# spu-schematic.net
KiCad netlist of a schematic drawn in EAGLE
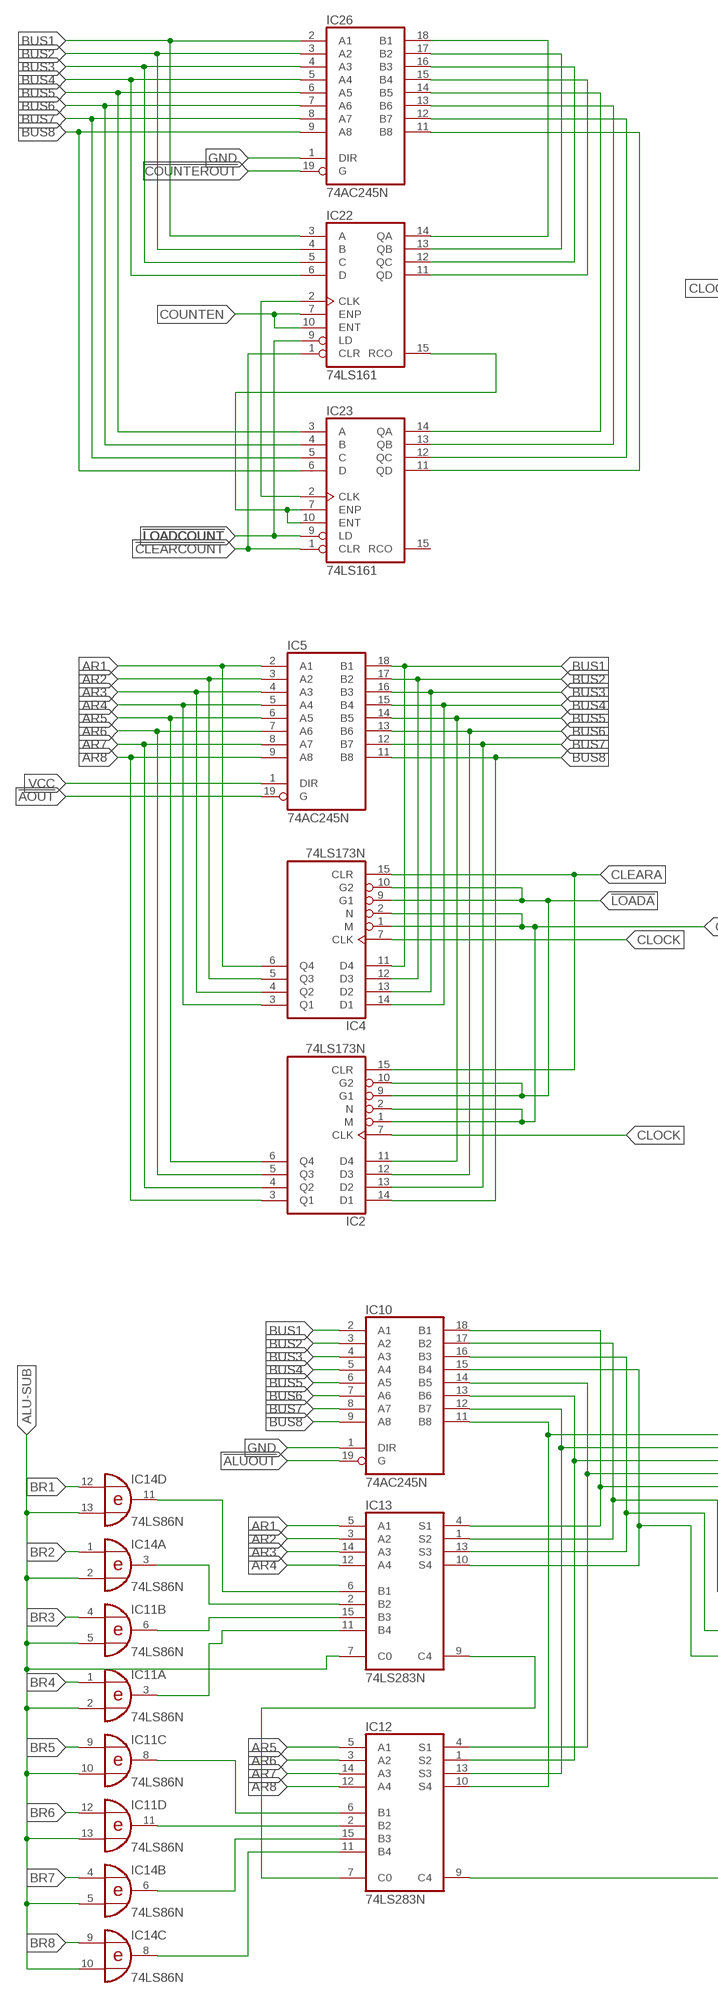
[diagram p0: schematic, sheet 1, part 1 of 2]
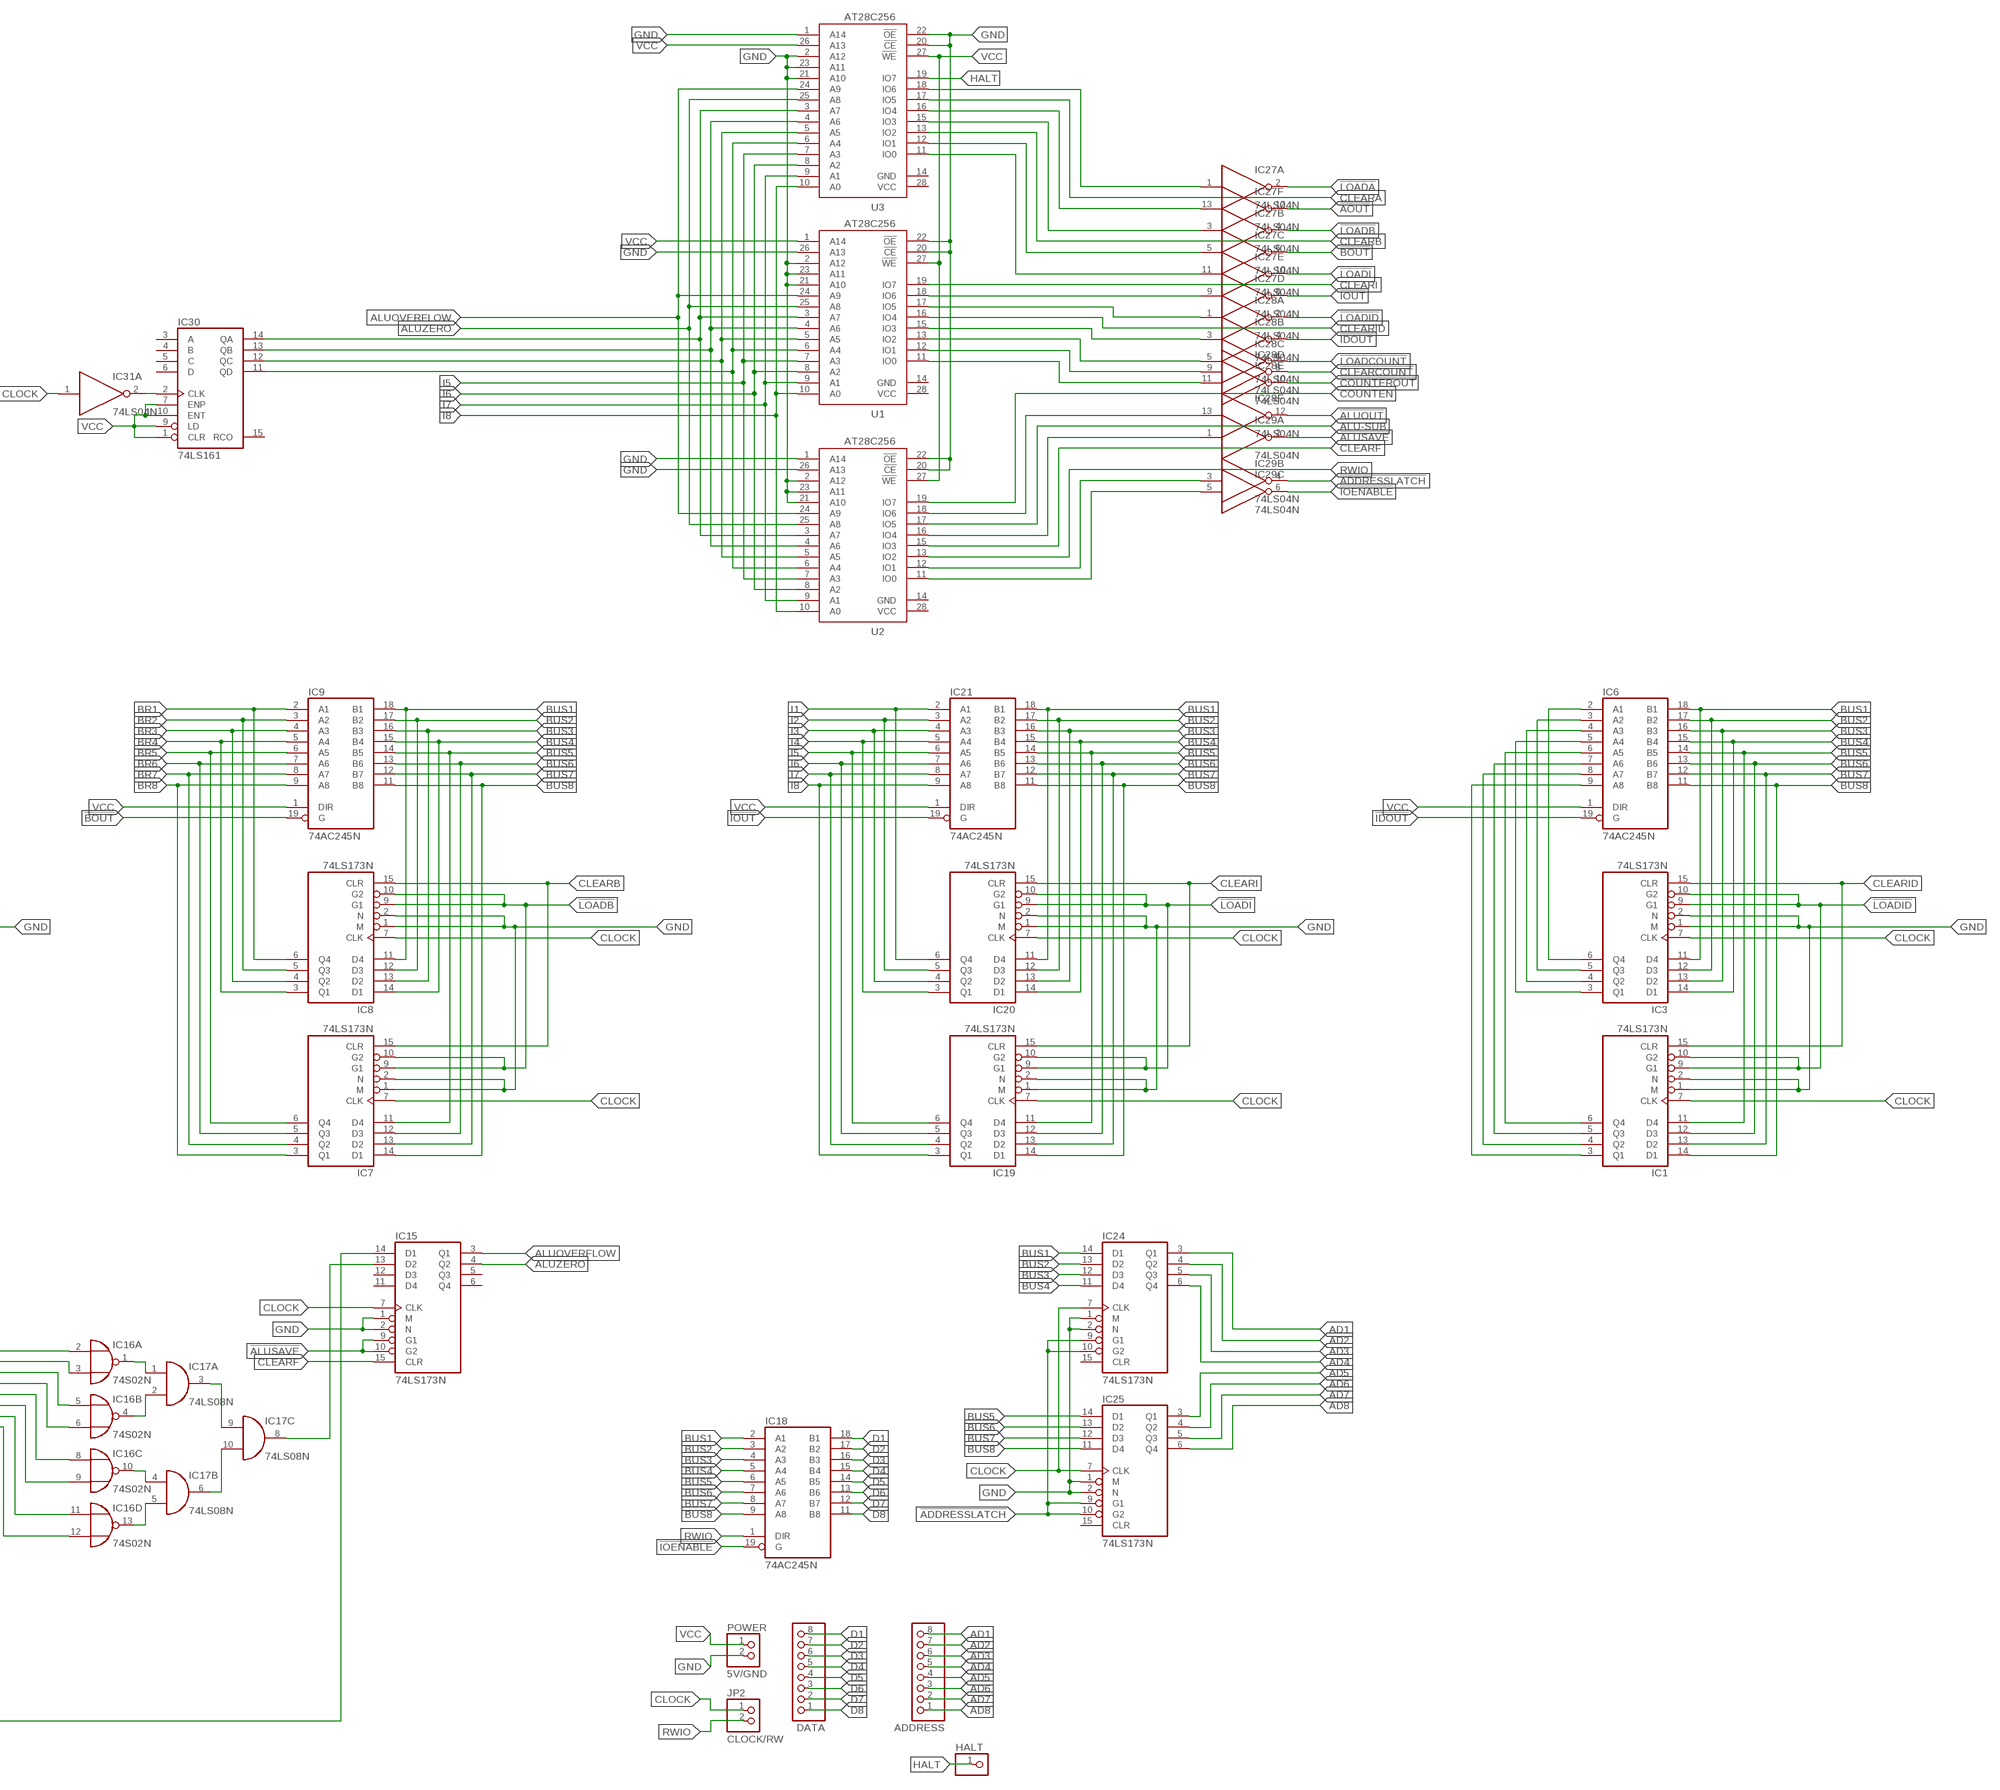
[diagram p1: schematic, sheet 1, part 2 of 2]

(export (version "E")
  (design (tool "Eeschema 10.0.6"))
  (components
    (comp (ref "ADDRESS")
      (value "PINHD-1X8")
      (footprint "eagle-import:1X08")
      (libsource (lib "eagle-import") (part "PINHD-1X8"))
    )
    (comp (ref "DATA")
      (value "PINHD-1X8")
      (footprint "eagle-import:1X08")
      (libsource (lib "eagle-import") (part "PINHD-1X8"))
    )
    (comp (ref "HALT")
      (value "PINHD-1X1")
      (footprint "eagle-import:1X01")
      (libsource (lib "eagle-import") (part "PINHD-1X1"))
    )
    (comp (ref "IC1")
      (value "74LS173N")
      (footprint "eagle-import:DIL16")
      (libsource (lib "eagle-import") (part "74173NLS"))
    )
    (comp (ref "IC2")
      (value "74LS173N")
      (footprint "eagle-import:DIL16")
      (libsource (lib "eagle-import") (part "74173NLS"))
    )
    (comp (ref "IC3")
      (value "74LS173N")
      (footprint "eagle-import:DIL16")
      (libsource (lib "eagle-import") (part "74173NLS"))
    )
    (comp (ref "IC4")
      (value "74LS173N")
      (footprint "eagle-import:DIL16")
      (libsource (lib "eagle-import") (part "74173NLS"))
    )
    (comp (ref "IC5")
      (value "74AC245N")
      (footprint "eagle-import:DIL20")
      (libsource (lib "eagle-import") (part "74245NAC"))
    )
    (comp (ref "IC6")
      (value "74AC245N")
      (footprint "eagle-import:DIL20")
      (libsource (lib "eagle-import") (part "74245NAC"))
    )
    (comp (ref "IC7")
      (value "74LS173N")
      (footprint "eagle-import:DIL16")
      (libsource (lib "eagle-import") (part "74173NLS"))
    )
    (comp (ref "IC8")
      (value "74LS173N")
      (footprint "eagle-import:DIL16")
      (libsource (lib "eagle-import") (part "74173NLS"))
    )
    (comp (ref "IC9")
      (value "74AC245N")
      (footprint "eagle-import:DIL20")
      (libsource (lib "eagle-import") (part "74245NAC"))
    )
    (comp (ref "IC10")
      (value "74AC245N")
      (footprint "eagle-import:DIL20")
      (libsource (lib "eagle-import") (part "74245NAC"))
    )
    (comp (ref "IC11")
      (value "74LS86N")
      (footprint "eagle-import:DIL14")
      (libsource (lib "eagle-import") (part "7486NLS"))
    )
    (comp (ref "IC12")
      (value "74LS283N")
      (footprint "eagle-import:DIL16")
      (libsource (lib "eagle-import") (part "74283NLS"))
    )
    (comp (ref "IC13")
      (value "74LS283N")
      (footprint "eagle-import:DIL16")
      (libsource (lib "eagle-import") (part "74283NLS"))
    )
    (comp (ref "IC14")
      (value "74LS86N")
      (footprint "eagle-import:DIL14")
      (libsource (lib "eagle-import") (part "7486NLS"))
    )
    (comp (ref "IC15")
      (value "74LS173N")
      (footprint "eagle-import:DIL16")
      (libsource (lib "eagle-import") (part "74173NLS"))
    )
    (comp (ref "IC16")
      (value "74S02N")
      (footprint "eagle-import:DIL14")
      (libsource (lib "eagle-import") (part "7402NS"))
    )
    (comp (ref "IC17")
      (value "74LS08N")
      (footprint "eagle-import:DIL14")
      (libsource (lib "eagle-import") (part "7408NLS"))
    )
    (comp (ref "IC18")
      (value "74AC245N")
      (footprint "eagle-import:DIL20")
      (libsource (lib "eagle-import") (part "74245NAC"))
    )
    (comp (ref "IC19")
      (value "74LS173N")
      (footprint "eagle-import:DIL16")
      (libsource (lib "eagle-import") (part "74173NLS"))
    )
    (comp (ref "IC20")
      (value "74LS173N")
      (footprint "eagle-import:DIL16")
      (libsource (lib "eagle-import") (part "74173NLS"))
    )
    (comp (ref "IC21")
      (value "74AC245N")
      (footprint "eagle-import:DIL20")
      (libsource (lib "eagle-import") (part "74245NAC"))
    )
    (comp (ref "IC22")
      (value "74LS161")
      (footprint "eagle-import:DIL16")
      (libsource (lib "eagle-import") (part "74160NHCT"))
    )
    (comp (ref "IC23")
      (value "74LS161")
      (footprint "eagle-import:DIL16")
      (libsource (lib "eagle-import") (part "74160NHCT"))
    )
    (comp (ref "IC24")
      (value "74LS173N")
      (footprint "eagle-import:DIL16")
      (libsource (lib "eagle-import") (part "74173NLS"))
    )
    (comp (ref "IC25")
      (value "74LS173N")
      (footprint "eagle-import:DIL16")
      (libsource (lib "eagle-import") (part "74173NLS"))
    )
    (comp (ref "IC26")
      (value "74AC245N")
      (footprint "eagle-import:DIL20")
      (libsource (lib "eagle-import") (part "74245NAC"))
    )
    (comp (ref "IC27")
      (value "74LS04N")
      (footprint "eagle-import:DIL14")
      (libsource (lib "eagle-import") (part "7404NLS"))
    )
    (comp (ref "IC28")
      (value "74LS04N")
      (footprint "eagle-import:DIL14")
      (libsource (lib "eagle-import") (part "7404NLS"))
    )
    (comp (ref "IC29")
      (value "74LS04N")
      (footprint "eagle-import:DIL14")
      (libsource (lib "eagle-import") (part "7404NLS"))
    )
    (comp (ref "IC30")
      (value "74LS161")
      (footprint "eagle-import:DIL16")
      (libsource (lib "eagle-import") (part "74160NHC"))
    )
    (comp (ref "IC31")
      (value "74LS04N")
      (footprint "eagle-import:DIL14")
      (libsource (lib "eagle-import") (part "7404NLS"))
    )
    (comp (ref "JP2")
      (value "CLOCK/RW")
      (footprint "eagle-import:1X02")
      (libsource (lib "eagle-import") (part "PINHD-1X2"))
    )
    (comp (ref "POWER")
      (value "5V/GND")
      (footprint "eagle-import:1X02")
      (libsource (lib "eagle-import") (part "PINHD-1X2"))
    )
    (comp (ref "U1")
      (value "AT28C256")
      (footprint "eagle-import:DIL28-6")
      (libsource (lib "eagle-import") (part "AT28C256"))
    )
    (comp (ref "U2")
      (value "AT28C256")
      (footprint "eagle-import:DIL28-6")
      (libsource (lib "eagle-import") (part "AT28C256"))
    )
    (comp (ref "U3")
      (value "AT28C256")
      (footprint "eagle-import:DIL28-6")
      (libsource (lib "eagle-import") (part "AT28C256"))
    )
  )
  (nets
    (net (code "1") (name "/~{ADDRESSLATCH}") (class "Default")
      (node (ref "IC24") (pin "10") (pinfunction "G2_10") (pintype "input"))
      (node (ref "IC24") (pin "9") (pinfunction "G1_9") (pintype "input"))
      (node (ref "IC25") (pin "10") (pinfunction "G2_10") (pintype "input"))
      (node (ref "IC25") (pin "9") (pinfunction "G1_9") (pintype "input"))
      (node (ref "IC29") (pin "4") (pinfunction "O_4") (pintype "output"))
    )
    (net (code "2") (name "/~{ALUOUT}") (class "Default")
      (node (ref "IC10") (pin "19") (pinfunction "G_19") (pintype "input"))
      (node (ref "IC28") (pin "12") (pinfunction "O_12") (pintype "output"))
    )
    (net (code "3") (name "/~{ALUSAVE}") (class "Default")
      (node (ref "IC15") (pin "10") (pinfunction "G2_10") (pintype "input"))
      (node (ref "IC15") (pin "9") (pinfunction "G1_9") (pintype "input"))
      (node (ref "IC29") (pin "2") (pinfunction "O_2") (pintype "output"))
    )
    (net (code "4") (name "/~{AOUT}") (class "Default")
      (node (ref "IC27") (pin "12") (pinfunction "O_12") (pintype "output"))
      (node (ref "IC5") (pin "19") (pinfunction "G_19") (pintype "input"))
    )
    (net (code "5") (name "/~{BOUT}") (class "Default")
      (node (ref "IC27") (pin "6") (pinfunction "O_6") (pintype "output"))
      (node (ref "IC9") (pin "19") (pinfunction "G_19") (pintype "input"))
    )
    (net (code "6") (name "/~{CLEARCOUNT}") (class "Default")
      (node (ref "IC22") (pin "1") (pinfunction "CLR_1") (pintype "input"))
      (node (ref "IC23") (pin "1") (pinfunction "CLR_1") (pintype "input"))
      (node (ref "IC28") (pin "8") (pinfunction "O_8") (pintype "output"))
    )
    (net (code "7") (name "/~{COUNTEROUT}") (class "Default")
      (node (ref "IC26") (pin "19") (pinfunction "G_19") (pintype "input"))
      (node (ref "IC28") (pin "10") (pinfunction "O_10") (pintype "output"))
    )
    (net (code "8") (name "/~{IDOUT}") (class "Default")
      (node (ref "IC28") (pin "4") (pinfunction "O_4") (pintype "output"))
      (node (ref "IC6") (pin "19") (pinfunction "G_19") (pintype "input"))
    )
    (net (code "9") (name "/~{IOENABLE}") (class "Default")
      (node (ref "IC18") (pin "19") (pinfunction "G_19") (pintype "input"))
      (node (ref "IC29") (pin "6") (pinfunction "O_6") (pintype "output"))
    )
    (net (code "10") (name "/~{IOUT}") (class "Default")
      (node (ref "IC21") (pin "19") (pinfunction "G_19") (pintype "input"))
      (node (ref "IC27") (pin "8") (pinfunction "O_8") (pintype "output"))
    )
    (net (code "11") (name "/~{LOADA}") (class "Default")
      (node (ref "IC2") (pin "10") (pinfunction "G2_10") (pintype "input"))
      (node (ref "IC2") (pin "9") (pinfunction "G1_9") (pintype "input"))
      (node (ref "IC27") (pin "2") (pinfunction "O_2") (pintype "output"))
      (node (ref "IC4") (pin "10") (pinfunction "G2_10") (pintype "input"))
      (node (ref "IC4") (pin "9") (pinfunction "G1_9") (pintype "input"))
    )
    (net (code "12") (name "/~{LOADB}") (class "Default")
      (node (ref "IC27") (pin "4") (pinfunction "O_4") (pintype "output"))
      (node (ref "IC7") (pin "10") (pinfunction "G2_10") (pintype "input"))
      (node (ref "IC7") (pin "9") (pinfunction "G1_9") (pintype "input"))
      (node (ref "IC8") (pin "10") (pinfunction "G2_10") (pintype "input"))
      (node (ref "IC8") (pin "9") (pinfunction "G1_9") (pintype "input"))
    )
    (net (code "13") (name "/~{LOADCOUNT}") (class "Default")
      (node (ref "IC22") (pin "9") (pinfunction "LD_9") (pintype "input"))
      (node (ref "IC23") (pin "9") (pinfunction "LD_9") (pintype "input"))
      (node (ref "IC28") (pin "6") (pinfunction "O_6") (pintype "output"))
    )
    (net (code "14") (name "/~{LOADID}") (class "Default")
      (node (ref "IC1") (pin "10") (pinfunction "G2_10") (pintype "input"))
      (node (ref "IC1") (pin "9") (pinfunction "G1_9") (pintype "input"))
      (node (ref "IC28") (pin "2") (pinfunction "O_2") (pintype "output"))
      (node (ref "IC3") (pin "10") (pinfunction "G2_10") (pintype "input"))
      (node (ref "IC3") (pin "9") (pinfunction "G1_9") (pintype "input"))
    )
    (net (code "15") (name "/~{LOADI}") (class "Default")
      (node (ref "IC19") (pin "10") (pinfunction "G2_10") (pintype "input"))
      (node (ref "IC19") (pin "9") (pinfunction "G1_9") (pintype "input"))
      (node (ref "IC20") (pin "10") (pinfunction "G2_10") (pintype "input"))
      (node (ref "IC20") (pin "9") (pinfunction "G1_9") (pintype "input"))
      (node (ref "IC27") (pin "10") (pinfunction "O_10") (pintype "output"))
    )
    (net (code "16") (name "AD1") (class "Default")
      (node (ref "ADDRESS") (pin "8") (pinfunction "8_8") (pintype "passive"))
      (node (ref "IC24") (pin "3") (pinfunction "Q1_3") (pintype "tri_state"))
    )
    (net (code "17") (name "AD2") (class "Default")
      (node (ref "ADDRESS") (pin "7") (pinfunction "7_7") (pintype "passive"))
      (node (ref "IC24") (pin "4") (pinfunction "Q2_4") (pintype "tri_state"))
    )
    (net (code "18") (name "AD3") (class "Default")
      (node (ref "ADDRESS") (pin "6") (pinfunction "6_6") (pintype "passive"))
      (node (ref "IC24") (pin "5") (pinfunction "Q3_5") (pintype "tri_state"))
    )
    (net (code "19") (name "AD4") (class "Default")
      (node (ref "ADDRESS") (pin "5") (pinfunction "5_5") (pintype "passive"))
      (node (ref "IC24") (pin "6") (pinfunction "Q4_6") (pintype "tri_state"))
    )
    (net (code "20") (name "AD5") (class "Default")
      (node (ref "ADDRESS") (pin "4") (pinfunction "4_4") (pintype "passive"))
      (node (ref "IC25") (pin "3") (pinfunction "Q1_3") (pintype "tri_state"))
    )
    (net (code "21") (name "AD6") (class "Default")
      (node (ref "ADDRESS") (pin "3") (pinfunction "3_3") (pintype "passive"))
      (node (ref "IC25") (pin "4") (pinfunction "Q2_4") (pintype "tri_state"))
    )
    (net (code "22") (name "AD7") (class "Default")
      (node (ref "ADDRESS") (pin "2") (pinfunction "2_2") (pintype "passive"))
      (node (ref "IC25") (pin "5") (pinfunction "Q3_5") (pintype "tri_state"))
    )
    (net (code "23") (name "AD8") (class "Default")
      (node (ref "ADDRESS") (pin "1") (pinfunction "1_1") (pintype "passive"))
      (node (ref "IC25") (pin "6") (pinfunction "Q4_6") (pintype "tri_state"))
    )
    (net (code "24") (name "ALU-SUB") (class "Default")
      (node (ref "IC11") (pin "10") (pinfunction "I1_10") (pintype "input"))
      (node (ref "IC11") (pin "13") (pinfunction "I1_13") (pintype "input"))
      (node (ref "IC11") (pin "2") (pinfunction "I1_2") (pintype "input"))
      (node (ref "IC11") (pin "5") (pinfunction "I1_5") (pintype "input"))
      (node (ref "IC13") (pin "7") (pinfunction "C0_7") (pintype "input"))
      (node (ref "IC14") (pin "10") (pinfunction "I1_10") (pintype "input"))
      (node (ref "IC14") (pin "13") (pinfunction "I1_13") (pintype "input"))
      (node (ref "IC14") (pin "2") (pinfunction "I1_2") (pintype "input"))
      (node (ref "IC14") (pin "5") (pinfunction "I1_5") (pintype "input"))
      (node (ref "U2") (pin "17") (pinfunction "IO5_17") (pintype "bidirectional"))
    )
    (net (code "25") (name "ALUOVERFLOW") (class "Default")
      (node (ref "IC15") (pin "3") (pinfunction "Q1_3") (pintype "tri_state"))
      (node (ref "U1") (pin "24") (pinfunction "A9_24") (pintype "bidirectional"))
      (node (ref "U2") (pin "24") (pinfunction "A9_24") (pintype "bidirectional"))
      (node (ref "U3") (pin "24") (pinfunction "A9_24") (pintype "bidirectional"))
    )
    (net (code "26") (name "ALUZERO") (class "Default")
      (node (ref "IC15") (pin "4") (pinfunction "Q2_4") (pintype "tri_state"))
      (node (ref "U1") (pin "25") (pinfunction "A8_25") (pintype "bidirectional"))
      (node (ref "U2") (pin "25") (pinfunction "A8_25") (pintype "bidirectional"))
      (node (ref "U3") (pin "25") (pinfunction "A8_25") (pintype "bidirectional"))
    )
    (net (code "27") (name "AR1") (class "Default")
      (node (ref "IC13") (pin "5") (pinfunction "A1_5") (pintype "input"))
      (node (ref "IC4") (pin "6") (pinfunction "Q4_6") (pintype "tri_state"))
      (node (ref "IC5") (pin "2") (pinfunction "A1_2") (pintype "bidirectional"))
    )
    (net (code "28") (name "AR2") (class "Default")
      (node (ref "IC13") (pin "3") (pinfunction "A2_3") (pintype "input"))
      (node (ref "IC4") (pin "5") (pinfunction "Q3_5") (pintype "tri_state"))
      (node (ref "IC5") (pin "3") (pinfunction "A2_3") (pintype "bidirectional"))
    )
    (net (code "29") (name "AR3") (class "Default")
      (node (ref "IC13") (pin "14") (pinfunction "A3_14") (pintype "input"))
      (node (ref "IC4") (pin "4") (pinfunction "Q2_4") (pintype "tri_state"))
      (node (ref "IC5") (pin "4") (pinfunction "A3_4") (pintype "bidirectional"))
    )
    (net (code "30") (name "AR4") (class "Default")
      (node (ref "IC13") (pin "12") (pinfunction "A4_12") (pintype "input"))
      (node (ref "IC4") (pin "3") (pinfunction "Q1_3") (pintype "tri_state"))
      (node (ref "IC5") (pin "5") (pinfunction "A4_5") (pintype "bidirectional"))
    )
    (net (code "31") (name "AR5") (class "Default")
      (node (ref "IC12") (pin "5") (pinfunction "A1_5") (pintype "input"))
      (node (ref "IC2") (pin "6") (pinfunction "Q4_6") (pintype "tri_state"))
      (node (ref "IC5") (pin "6") (pinfunction "A5_6") (pintype "bidirectional"))
    )
    (net (code "32") (name "AR6") (class "Default")
      (node (ref "IC12") (pin "3") (pinfunction "A2_3") (pintype "input"))
      (node (ref "IC2") (pin "5") (pinfunction "Q3_5") (pintype "tri_state"))
      (node (ref "IC5") (pin "7") (pinfunction "A6_7") (pintype "bidirectional"))
    )
    (net (code "33") (name "AR7") (class "Default")
      (node (ref "IC12") (pin "14") (pinfunction "A3_14") (pintype "input"))
      (node (ref "IC2") (pin "4") (pinfunction "Q2_4") (pintype "tri_state"))
      (node (ref "IC5") (pin "8") (pinfunction "A7_8") (pintype "bidirectional"))
    )
    (net (code "34") (name "AR8") (class "Default")
      (node (ref "IC12") (pin "12") (pinfunction "A4_12") (pintype "input"))
      (node (ref "IC2") (pin "3") (pinfunction "Q1_3") (pintype "tri_state"))
      (node (ref "IC5") (pin "9") (pinfunction "A8_9") (pintype "bidirectional"))
    )
    (net (code "35") (name "BR1") (class "Default")
      (node (ref "IC14") (pin "12") (pinfunction "I0_12") (pintype "input"))
      (node (ref "IC8") (pin "6") (pinfunction "Q4_6") (pintype "tri_state"))
      (node (ref "IC9") (pin "2") (pinfunction "A1_2") (pintype "bidirectional"))
    )
    (net (code "36") (name "BR2") (class "Default")
      (node (ref "IC14") (pin "1") (pinfunction "I0_1") (pintype "input"))
      (node (ref "IC8") (pin "5") (pinfunction "Q3_5") (pintype "tri_state"))
      (node (ref "IC9") (pin "3") (pinfunction "A2_3") (pintype "bidirectional"))
    )
    (net (code "37") (name "BR3") (class "Default")
      (node (ref "IC11") (pin "4") (pinfunction "I0_4") (pintype "input"))
      (node (ref "IC8") (pin "4") (pinfunction "Q2_4") (pintype "tri_state"))
      (node (ref "IC9") (pin "4") (pinfunction "A3_4") (pintype "bidirectional"))
    )
    (net (code "38") (name "BR4") (class "Default")
      (node (ref "IC11") (pin "1") (pinfunction "I0_1") (pintype "input"))
      (node (ref "IC8") (pin "3") (pinfunction "Q1_3") (pintype "tri_state"))
      (node (ref "IC9") (pin "5") (pinfunction "A4_5") (pintype "bidirectional"))
    )
    (net (code "39") (name "BR5") (class "Default")
      (node (ref "IC11") (pin "9") (pinfunction "I0_9") (pintype "input"))
      (node (ref "IC7") (pin "6") (pinfunction "Q4_6") (pintype "tri_state"))
      (node (ref "IC9") (pin "6") (pinfunction "A5_6") (pintype "bidirectional"))
    )
    (net (code "40") (name "BR6") (class "Default")
      (node (ref "IC11") (pin "12") (pinfunction "I0_12") (pintype "input"))
      (node (ref "IC7") (pin "5") (pinfunction "Q3_5") (pintype "tri_state"))
      (node (ref "IC9") (pin "7") (pinfunction "A6_7") (pintype "bidirectional"))
    )
    (net (code "41") (name "BR7") (class "Default")
      (node (ref "IC14") (pin "4") (pinfunction "I0_4") (pintype "input"))
      (node (ref "IC7") (pin "4") (pinfunction "Q2_4") (pintype "tri_state"))
      (node (ref "IC9") (pin "8") (pinfunction "A7_8") (pintype "bidirectional"))
    )
    (net (code "42") (name "BR8") (class "Default")
      (node (ref "IC14") (pin "9") (pinfunction "I0_9") (pintype "input"))
      (node (ref "IC7") (pin "3") (pinfunction "Q1_3") (pintype "tri_state"))
      (node (ref "IC9") (pin "9") (pinfunction "A8_9") (pintype "bidirectional"))
    )
    (net (code "43") (name "BUS1") (class "Default")
      (node (ref "IC10") (pin "2") (pinfunction "A1_2") (pintype "bidirectional"))
      (node (ref "IC18") (pin "2") (pinfunction "A1_2") (pintype "bidirectional"))
      (node (ref "IC20") (pin "11") (pinfunction "D4_11") (pintype "input"))
      (node (ref "IC21") (pin "18") (pinfunction "B1_18") (pintype "bidirectional"))
      (node (ref "IC22") (pin "3") (pinfunction "A_3") (pintype "input"))
      (node (ref "IC24") (pin "14") (pinfunction "D1_14") (pintype "input"))
      (node (ref "IC26") (pin "2") (pinfunction "A1_2") (pintype "bidirectional"))
      (node (ref "IC3") (pin "11") (pinfunction "D4_11") (pintype "input"))
      (node (ref "IC4") (pin "11") (pinfunction "D4_11") (pintype "input"))
      (node (ref "IC5") (pin "18") (pinfunction "B1_18") (pintype "bidirectional"))
      (node (ref "IC6") (pin "18") (pinfunction "B1_18") (pintype "bidirectional"))
      (node (ref "IC8") (pin "11") (pinfunction "D4_11") (pintype "input"))
      (node (ref "IC9") (pin "18") (pinfunction "B1_18") (pintype "bidirectional"))
    )
    (net (code "44") (name "BUS2") (class "Default")
      (node (ref "IC10") (pin "3") (pinfunction "A2_3") (pintype "bidirectional"))
      (node (ref "IC18") (pin "3") (pinfunction "A2_3") (pintype "bidirectional"))
      (node (ref "IC20") (pin "12") (pinfunction "D3_12") (pintype "input"))
      (node (ref "IC21") (pin "17") (pinfunction "B2_17") (pintype "bidirectional"))
      (node (ref "IC22") (pin "4") (pinfunction "B_4") (pintype "input"))
      (node (ref "IC24") (pin "13") (pinfunction "D2_13") (pintype "input"))
      (node (ref "IC26") (pin "3") (pinfunction "A2_3") (pintype "bidirectional"))
      (node (ref "IC3") (pin "12") (pinfunction "D3_12") (pintype "input"))
      (node (ref "IC4") (pin "12") (pinfunction "D3_12") (pintype "input"))
      (node (ref "IC5") (pin "17") (pinfunction "B2_17") (pintype "bidirectional"))
      (node (ref "IC6") (pin "17") (pinfunction "B2_17") (pintype "bidirectional"))
      (node (ref "IC8") (pin "12") (pinfunction "D3_12") (pintype "input"))
      (node (ref "IC9") (pin "17") (pinfunction "B2_17") (pintype "bidirectional"))
    )
    (net (code "45") (name "BUS3") (class "Default")
      (node (ref "IC10") (pin "4") (pinfunction "A3_4") (pintype "bidirectional"))
      (node (ref "IC18") (pin "4") (pinfunction "A3_4") (pintype "bidirectional"))
      (node (ref "IC20") (pin "13") (pinfunction "D2_13") (pintype "input"))
      (node (ref "IC21") (pin "16") (pinfunction "B3_16") (pintype "bidirectional"))
      (node (ref "IC22") (pin "5") (pinfunction "C_5") (pintype "input"))
      (node (ref "IC24") (pin "12") (pinfunction "D3_12") (pintype "input"))
      (node (ref "IC26") (pin "4") (pinfunction "A3_4") (pintype "bidirectional"))
      (node (ref "IC3") (pin "13") (pinfunction "D2_13") (pintype "input"))
      (node (ref "IC4") (pin "13") (pinfunction "D2_13") (pintype "input"))
      (node (ref "IC5") (pin "16") (pinfunction "B3_16") (pintype "bidirectional"))
      (node (ref "IC6") (pin "16") (pinfunction "B3_16") (pintype "bidirectional"))
      (node (ref "IC8") (pin "13") (pinfunction "D2_13") (pintype "input"))
      (node (ref "IC9") (pin "16") (pinfunction "B3_16") (pintype "bidirectional"))
    )
    (net (code "46") (name "BUS4") (class "Default")
      (node (ref "IC10") (pin "5") (pinfunction "A4_5") (pintype "bidirectional"))
      (node (ref "IC18") (pin "5") (pinfunction "A4_5") (pintype "bidirectional"))
      (node (ref "IC20") (pin "14") (pinfunction "D1_14") (pintype "input"))
      (node (ref "IC21") (pin "15") (pinfunction "B4_15") (pintype "bidirectional"))
      (node (ref "IC22") (pin "6") (pinfunction "D_6") (pintype "input"))
      (node (ref "IC24") (pin "11") (pinfunction "D4_11") (pintype "input"))
      (node (ref "IC26") (pin "5") (pinfunction "A4_5") (pintype "bidirectional"))
      (node (ref "IC3") (pin "14") (pinfunction "D1_14") (pintype "input"))
      (node (ref "IC4") (pin "14") (pinfunction "D1_14") (pintype "input"))
      (node (ref "IC5") (pin "15") (pinfunction "B4_15") (pintype "bidirectional"))
      (node (ref "IC6") (pin "15") (pinfunction "B4_15") (pintype "bidirectional"))
      (node (ref "IC8") (pin "14") (pinfunction "D1_14") (pintype "input"))
      (node (ref "IC9") (pin "15") (pinfunction "B4_15") (pintype "bidirectional"))
    )
    (net (code "47") (name "BUS5") (class "Default")
      (node (ref "IC1") (pin "11") (pinfunction "D4_11") (pintype "input"))
      (node (ref "IC10") (pin "6") (pinfunction "A5_6") (pintype "bidirectional"))
      (node (ref "IC18") (pin "6") (pinfunction "A5_6") (pintype "bidirectional"))
      (node (ref "IC19") (pin "11") (pinfunction "D4_11") (pintype "input"))
      (node (ref "IC2") (pin "11") (pinfunction "D4_11") (pintype "input"))
      (node (ref "IC21") (pin "14") (pinfunction "B5_14") (pintype "bidirectional"))
      (node (ref "IC23") (pin "3") (pinfunction "A_3") (pintype "input"))
      (node (ref "IC25") (pin "14") (pinfunction "D1_14") (pintype "input"))
      (node (ref "IC26") (pin "6") (pinfunction "A5_6") (pintype "bidirectional"))
      (node (ref "IC5") (pin "14") (pinfunction "B5_14") (pintype "bidirectional"))
      (node (ref "IC6") (pin "14") (pinfunction "B5_14") (pintype "bidirectional"))
      (node (ref "IC7") (pin "11") (pinfunction "D4_11") (pintype "input"))
      (node (ref "IC9") (pin "14") (pinfunction "B5_14") (pintype "bidirectional"))
    )
    (net (code "48") (name "BUS6") (class "Default")
      (node (ref "IC1") (pin "12") (pinfunction "D3_12") (pintype "input"))
      (node (ref "IC10") (pin "7") (pinfunction "A6_7") (pintype "bidirectional"))
      (node (ref "IC18") (pin "7") (pinfunction "A6_7") (pintype "bidirectional"))
      (node (ref "IC19") (pin "12") (pinfunction "D3_12") (pintype "input"))
      (node (ref "IC2") (pin "12") (pinfunction "D3_12") (pintype "input"))
      (node (ref "IC21") (pin "13") (pinfunction "B6_13") (pintype "bidirectional"))
      (node (ref "IC23") (pin "4") (pinfunction "B_4") (pintype "input"))
      (node (ref "IC25") (pin "13") (pinfunction "D2_13") (pintype "input"))
      (node (ref "IC26") (pin "7") (pinfunction "A6_7") (pintype "bidirectional"))
      (node (ref "IC5") (pin "13") (pinfunction "B6_13") (pintype "bidirectional"))
      (node (ref "IC6") (pin "13") (pinfunction "B6_13") (pintype "bidirectional"))
      (node (ref "IC7") (pin "12") (pinfunction "D3_12") (pintype "input"))
      (node (ref "IC9") (pin "13") (pinfunction "B6_13") (pintype "bidirectional"))
    )
    (net (code "49") (name "BUS7") (class "Default")
      (node (ref "IC1") (pin "13") (pinfunction "D2_13") (pintype "input"))
      (node (ref "IC10") (pin "8") (pinfunction "A7_8") (pintype "bidirectional"))
      (node (ref "IC18") (pin "8") (pinfunction "A7_8") (pintype "bidirectional"))
      (node (ref "IC19") (pin "13") (pinfunction "D2_13") (pintype "input"))
      (node (ref "IC2") (pin "13") (pinfunction "D2_13") (pintype "input"))
      (node (ref "IC21") (pin "12") (pinfunction "B7_12") (pintype "bidirectional"))
      (node (ref "IC23") (pin "5") (pinfunction "C_5") (pintype "input"))
      (node (ref "IC25") (pin "12") (pinfunction "D3_12") (pintype "input"))
      (node (ref "IC26") (pin "8") (pinfunction "A7_8") (pintype "bidirectional"))
      (node (ref "IC5") (pin "12") (pinfunction "B7_12") (pintype "bidirectional"))
      (node (ref "IC6") (pin "12") (pinfunction "B7_12") (pintype "bidirectional"))
      (node (ref "IC7") (pin "13") (pinfunction "D2_13") (pintype "input"))
      (node (ref "IC9") (pin "12") (pinfunction "B7_12") (pintype "bidirectional"))
    )
    (net (code "50") (name "BUS8") (class "Default")
      (node (ref "IC1") (pin "14") (pinfunction "D1_14") (pintype "input"))
      (node (ref "IC10") (pin "9") (pinfunction "A8_9") (pintype "bidirectional"))
      (node (ref "IC18") (pin "9") (pinfunction "A8_9") (pintype "bidirectional"))
      (node (ref "IC19") (pin "14") (pinfunction "D1_14") (pintype "input"))
      (node (ref "IC2") (pin "14") (pinfunction "D1_14") (pintype "input"))
      (node (ref "IC21") (pin "11") (pinfunction "B8_11") (pintype "bidirectional"))
      (node (ref "IC23") (pin "6") (pinfunction "D_6") (pintype "input"))
      (node (ref "IC25") (pin "11") (pinfunction "D4_11") (pintype "input"))
      (node (ref "IC26") (pin "9") (pinfunction "A8_9") (pintype "bidirectional"))
      (node (ref "IC5") (pin "11") (pinfunction "B8_11") (pintype "bidirectional"))
      (node (ref "IC6") (pin "11") (pinfunction "B8_11") (pintype "bidirectional"))
      (node (ref "IC7") (pin "14") (pinfunction "D1_14") (pintype "input"))
      (node (ref "IC9") (pin "11") (pinfunction "B8_11") (pintype "bidirectional"))
    )
    (net (code "51") (name "CLEARA") (class "Default")
      (node (ref "IC2") (pin "15") (pinfunction "CLR_15") (pintype "input"))
      (node (ref "IC4") (pin "15") (pinfunction "CLR_15") (pintype "input"))
      (node (ref "U3") (pin "17") (pinfunction "IO5_17") (pintype "bidirectional"))
    )
    (net (code "52") (name "CLEARB") (class "Default")
      (node (ref "IC7") (pin "15") (pinfunction "CLR_15") (pintype "input"))
      (node (ref "IC8") (pin "15") (pinfunction "CLR_15") (pintype "input"))
      (node (ref "U3") (pin "13") (pinfunction "IO2_13") (pintype "bidirectional"))
    )
    (net (code "53") (name "CLEARF") (class "Default")
      (node (ref "IC15") (pin "15") (pinfunction "CLR_15") (pintype "input"))
      (node (ref "U2") (pin "15") (pinfunction "IO3_15") (pintype "bidirectional"))
    )
    (net (code "54") (name "CLEARI") (class "Default")
      (node (ref "IC19") (pin "15") (pinfunction "CLR_15") (pintype "input"))
      (node (ref "IC20") (pin "15") (pinfunction "CLR_15") (pintype "input"))
      (node (ref "U1") (pin "19") (pinfunction "IO7_19") (pintype "bidirectional"))
    )
    (net (code "55") (name "CLEARID") (class "Default")
      (node (ref "IC1") (pin "15") (pinfunction "CLR_15") (pintype "input"))
      (node (ref "IC3") (pin "15") (pinfunction "CLR_15") (pintype "input"))
      (node (ref "U1") (pin "16") (pinfunction "IO4_16") (pintype "bidirectional"))
    )
    (net (code "56") (name "CLOCK") (class "Default")
      (node (ref "IC1") (pin "7") (pinfunction "CLK_7") (pintype "input"))
      (node (ref "IC15") (pin "7") (pinfunction "CLK_7") (pintype "input"))
      (node (ref "IC19") (pin "7") (pinfunction "CLK_7") (pintype "input"))
      (node (ref "IC2") (pin "7") (pinfunction "CLK_7") (pintype "input"))
      (node (ref "IC20") (pin "7") (pinfunction "CLK_7") (pintype "input"))
      (node (ref "IC24") (pin "7") (pinfunction "CLK_7") (pintype "input"))
      (node (ref "IC25") (pin "7") (pinfunction "CLK_7") (pintype "input"))
      (node (ref "IC3") (pin "7") (pinfunction "CLK_7") (pintype "input"))
      (node (ref "IC30") (pin "2") (pinfunction "CLK_2") (pintype "input"))
      (node (ref "IC31") (pin "1") (pinfunction "I_1") (pintype "input"))
      (node (ref "IC31") (pin "2") (pinfunction "O_2") (pintype "output"))
      (node (ref "IC4") (pin "7") (pinfunction "CLK_7") (pintype "input"))
      (node (ref "IC7") (pin "7") (pinfunction "CLK_7") (pintype "input"))
      (node (ref "IC8") (pin "7") (pinfunction "CLK_7") (pintype "input"))
      (node (ref "JP2") (pin "1") (pinfunction "1_1") (pintype "passive"))
    )
    (net (code "57") (name "COUNTEN") (class "Default")
      (node (ref "IC22") (pin "10") (pinfunction "ENT_10") (pintype "input"))
      (node (ref "IC22") (pin "7") (pinfunction "ENP_7") (pintype "input"))
      (node (ref "U2") (pin "19") (pinfunction "IO7_19") (pintype "bidirectional"))
    )
    (net (code "58") (name "D1") (class "Default")
      (node (ref "DATA") (pin "8") (pinfunction "8_8") (pintype "passive"))
      (node (ref "IC18") (pin "18") (pinfunction "B1_18") (pintype "bidirectional"))
    )
    (net (code "59") (name "D2") (class "Default")
      (node (ref "DATA") (pin "7") (pinfunction "7_7") (pintype "passive"))
      (node (ref "IC18") (pin "17") (pinfunction "B2_17") (pintype "bidirectional"))
    )
    (net (code "60") (name "D3") (class "Default")
      (node (ref "DATA") (pin "6") (pinfunction "6_6") (pintype "passive"))
      (node (ref "IC18") (pin "16") (pinfunction "B3_16") (pintype "bidirectional"))
    )
    (net (code "61") (name "D4") (class "Default")
      (node (ref "DATA") (pin "5") (pinfunction "5_5") (pintype "passive"))
      (node (ref "IC18") (pin "15") (pinfunction "B4_15") (pintype "bidirectional"))
    )
    (net (code "62") (name "D5") (class "Default")
      (node (ref "DATA") (pin "4") (pinfunction "4_4") (pintype "passive"))
      (node (ref "IC18") (pin "14") (pinfunction "B5_14") (pintype "bidirectional"))
    )
    (net (code "63") (name "D6") (class "Default")
      (node (ref "DATA") (pin "3") (pinfunction "3_3") (pintype "passive"))
      (node (ref "IC18") (pin "13") (pinfunction "B6_13") (pintype "bidirectional"))
    )
    (net (code "64") (name "D7") (class "Default")
      (node (ref "DATA") (pin "2") (pinfunction "2_2") (pintype "passive"))
      (node (ref "IC18") (pin "12") (pinfunction "B7_12") (pintype "bidirectional"))
    )
    (net (code "65") (name "D8") (class "Default")
      (node (ref "DATA") (pin "1") (pinfunction "1_1") (pintype "passive"))
      (node (ref "IC18") (pin "11") (pinfunction "B8_11") (pintype "bidirectional"))
    )
    (net (code "66") (name "GND") (class "Default")
      (node (ref "IC1") (pin "1") (pinfunction "M_1") (pintype "input"))
      (node (ref "IC1") (pin "2") (pinfunction "N_2") (pintype "input"))
      (node (ref "IC10") (pin "1") (pinfunction "DIR_1") (pintype "input"))
      (node (ref "IC15") (pin "1") (pinfunction "M_1") (pintype "input"))
      (node (ref "IC15") (pin "2") (pinfunction "N_2") (pintype "input"))
      (node (ref "IC19") (pin "1") (pinfunction "M_1") (pintype "input"))
      (node (ref "IC19") (pin "2") (pinfunction "N_2") (pintype "input"))
      (node (ref "IC2") (pin "1") (pinfunction "M_1") (pintype "input"))
      (node (ref "IC2") (pin "2") (pinfunction "N_2") (pintype "input"))
      (node (ref "IC20") (pin "1") (pinfunction "M_1") (pintype "input"))
      (node (ref "IC20") (pin "2") (pinfunction "N_2") (pintype "input"))
      (node (ref "IC24") (pin "1") (pinfunction "M_1") (pintype "input"))
      (node (ref "IC24") (pin "2") (pinfunction "N_2") (pintype "input"))
      (node (ref "IC25") (pin "1") (pinfunction "M_1") (pintype "input"))
      (node (ref "IC25") (pin "2") (pinfunction "N_2") (pintype "input"))
      (node (ref "IC26") (pin "1") (pinfunction "DIR_1") (pintype "input"))
      (node (ref "IC3") (pin "1") (pinfunction "M_1") (pintype "input"))
      (node (ref "IC3") (pin "2") (pinfunction "N_2") (pintype "input"))
      (node (ref "IC4") (pin "1") (pinfunction "M_1") (pintype "input"))
      (node (ref "IC4") (pin "2") (pinfunction "N_2") (pintype "input"))
      (node (ref "IC7") (pin "1") (pinfunction "M_1") (pintype "input"))
      (node (ref "IC7") (pin "2") (pinfunction "N_2") (pintype "input"))
      (node (ref "IC8") (pin "1") (pinfunction "M_1") (pintype "input"))
      (node (ref "IC8") (pin "2") (pinfunction "N_2") (pintype "input"))
      (node (ref "POWER") (pin "2") (pinfunction "2_2") (pintype "passive"))
      (node (ref "U1") (pin "2") (pinfunction "A12_2") (pintype "bidirectional"))
      (node (ref "U1") (pin "20") (pinfunction "~{CE}_20") (pintype "bidirectional"))
      (node (ref "U1") (pin "21") (pinfunction "A10_21") (pintype "bidirectional"))
      (node (ref "U1") (pin "22") (pinfunction "~{OE}_22") (pintype "bidirectional"))
      (node (ref "U1") (pin "23") (pinfunction "A11_23") (pintype "bidirectional"))
      (node (ref "U1") (pin "26") (pinfunction "A13_26") (pintype "bidirectional"))
      (node (ref "U2") (pin "1") (pinfunction "A14_1") (pintype "bidirectional"))
      (node (ref "U2") (pin "2") (pinfunction "A12_2") (pintype "bidirectional"))
      (node (ref "U2") (pin "20") (pinfunction "~{CE}_20") (pintype "bidirectional"))
      (node (ref "U2") (pin "21") (pinfunction "A10_21") (pintype "bidirectional"))
      (node (ref "U2") (pin "22") (pinfunction "~{OE}_22") (pintype "bidirectional"))
      (node (ref "U2") (pin "23") (pinfunction "A11_23") (pintype "bidirectional"))
      (node (ref "U2") (pin "26") (pinfunction "A13_26") (pintype "bidirectional"))
      (node (ref "U3") (pin "1") (pinfunction "A14_1") (pintype "bidirectional"))
      (node (ref "U3") (pin "2") (pinfunction "A12_2") (pintype "bidirectional"))
      (node (ref "U3") (pin "20") (pinfunction "~{CE}_20") (pintype "bidirectional"))
      (node (ref "U3") (pin "21") (pinfunction "A10_21") (pintype "bidirectional"))
      (node (ref "U3") (pin "22") (pinfunction "~{OE}_22") (pintype "bidirectional"))
      (node (ref "U3") (pin "23") (pinfunction "A11_23") (pintype "bidirectional"))
    )
    (net (code "67") (name "HALT") (class "Default")
      (node (ref "HALT") (pin "1") (pinfunction "1_1") (pintype "passive"))
      (node (ref "U3") (pin "19") (pinfunction "IO7_19") (pintype "bidirectional"))
    )
    (net (code "68") (name "I1") (class "Default")
      (node (ref "IC20") (pin "6") (pinfunction "Q4_6") (pintype "tri_state"))
      (node (ref "IC21") (pin "2") (pinfunction "A1_2") (pintype "bidirectional"))
    )
    (net (code "69") (name "I2") (class "Default")
      (node (ref "IC20") (pin "5") (pinfunction "Q3_5") (pintype "tri_state"))
      (node (ref "IC21") (pin "3") (pinfunction "A2_3") (pintype "bidirectional"))
    )
    (net (code "70") (name "I3") (class "Default")
      (node (ref "IC20") (pin "4") (pinfunction "Q2_4") (pintype "tri_state"))
      (node (ref "IC21") (pin "4") (pinfunction "A3_4") (pintype "bidirectional"))
    )
    (net (code "71") (name "I4") (class "Default")
      (node (ref "IC20") (pin "3") (pinfunction "Q1_3") (pintype "tri_state"))
      (node (ref "IC21") (pin "5") (pinfunction "A4_5") (pintype "bidirectional"))
    )
    (net (code "72") (name "I5") (class "Default")
      (node (ref "IC19") (pin "6") (pinfunction "Q4_6") (pintype "tri_state"))
      (node (ref "IC21") (pin "6") (pinfunction "A5_6") (pintype "bidirectional"))
      (node (ref "U1") (pin "7") (pinfunction "A3_7") (pintype "bidirectional"))
      (node (ref "U2") (pin "7") (pinfunction "A3_7") (pintype "bidirectional"))
      (node (ref "U3") (pin "7") (pinfunction "A3_7") (pintype "bidirectional"))
    )
    (net (code "73") (name "I6") (class "Default")
      (node (ref "IC19") (pin "5") (pinfunction "Q3_5") (pintype "tri_state"))
      (node (ref "IC21") (pin "7") (pinfunction "A6_7") (pintype "bidirectional"))
      (node (ref "U1") (pin "8") (pinfunction "A2_8") (pintype "bidirectional"))
      (node (ref "U2") (pin "8") (pinfunction "A2_8") (pintype "bidirectional"))
      (node (ref "U3") (pin "8") (pinfunction "A2_8") (pintype "bidirectional"))
    )
    (net (code "74") (name "I7") (class "Default")
      (node (ref "IC19") (pin "4") (pinfunction "Q2_4") (pintype "tri_state"))
      (node (ref "IC21") (pin "8") (pinfunction "A7_8") (pintype "bidirectional"))
      (node (ref "U1") (pin "9") (pinfunction "A1_9") (pintype "bidirectional"))
      (node (ref "U2") (pin "9") (pinfunction "A1_9") (pintype "bidirectional"))
      (node (ref "U3") (pin "9") (pinfunction "A1_9") (pintype "bidirectional"))
    )
    (net (code "75") (name "I8") (class "Default")
      (node (ref "IC19") (pin "3") (pinfunction "Q1_3") (pintype "tri_state"))
      (node (ref "IC21") (pin "9") (pinfunction "A8_9") (pintype "bidirectional"))
      (node (ref "U1") (pin "10") (pinfunction "A0_10") (pintype "bidirectional"))
      (node (ref "U2") (pin "10") (pinfunction "A0_10") (pintype "bidirectional"))
      (node (ref "U3") (pin "10") (pinfunction "A0_10") (pintype "bidirectional"))
    )
    (net (code "76") (name "Net-(IC1A-Q1)") (class "Default")
      (node (ref "IC1") (pin "3") (pinfunction "Q1_3") (pintype "tri_state"))
      (node (ref "IC6") (pin "9") (pinfunction "A8_9") (pintype "bidirectional"))
    )
    (net (code "77") (name "Net-(IC1A-Q2)") (class "Default")
      (node (ref "IC1") (pin "4") (pinfunction "Q2_4") (pintype "tri_state"))
      (node (ref "IC6") (pin "8") (pinfunction "A7_8") (pintype "bidirectional"))
    )
    (net (code "78") (name "Net-(IC1A-Q3)") (class "Default")
      (node (ref "IC1") (pin "5") (pinfunction "Q3_5") (pintype "tri_state"))
      (node (ref "IC6") (pin "7") (pinfunction "A6_7") (pintype "bidirectional"))
    )
    (net (code "79") (name "Net-(IC1A-Q4)") (class "Default")
      (node (ref "IC1") (pin "6") (pinfunction "Q4_6") (pintype "tri_state"))
      (node (ref "IC6") (pin "6") (pinfunction "A5_6") (pintype "bidirectional"))
    )
    (net (code "80") (name "Net-(IC3A-Q1)") (class "Default")
      (node (ref "IC3") (pin "3") (pinfunction "Q1_3") (pintype "tri_state"))
      (node (ref "IC6") (pin "5") (pinfunction "A4_5") (pintype "bidirectional"))
    )
    (net (code "81") (name "Net-(IC3A-Q2)") (class "Default")
      (node (ref "IC3") (pin "4") (pinfunction "Q2_4") (pintype "tri_state"))
      (node (ref "IC6") (pin "4") (pinfunction "A3_4") (pintype "bidirectional"))
    )
    (net (code "82") (name "Net-(IC3A-Q3)") (class "Default")
      (node (ref "IC3") (pin "5") (pinfunction "Q3_5") (pintype "tri_state"))
      (node (ref "IC6") (pin "3") (pinfunction "A2_3") (pintype "bidirectional"))
    )
    (net (code "83") (name "Net-(IC3A-Q4)") (class "Default")
      (node (ref "IC3") (pin "6") (pinfunction "Q4_6") (pintype "tri_state"))
      (node (ref "IC6") (pin "2") (pinfunction "A1_2") (pintype "bidirectional"))
    )
    (net (code "84") (name "Net-(IC10A-B1)") (class "Default")
      (node (ref "IC10") (pin "18") (pinfunction "B1_18") (pintype "bidirectional"))
      (node (ref "IC13") (pin "4") (pinfunction "S1_4") (pintype "output"))
      (node (ref "IC16") (pin "8") (pinfunction "I0_8") (pintype "input"))
    )
    (net (code "85") (name "Net-(IC10A-B2)") (class "Default")
      (node (ref "IC10") (pin "17") (pinfunction "B2_17") (pintype "bidirectional"))
      (node (ref "IC13") (pin "1") (pinfunction "S2_1") (pintype "output"))
      (node (ref "IC16") (pin "9") (pinfunction "I1_9") (pintype "input"))
    )
    (net (code "86") (name "Net-(IC10A-B3)") (class "Default")
      (node (ref "IC10") (pin "16") (pinfunction "B3_16") (pintype "bidirectional"))
      (node (ref "IC13") (pin "13") (pinfunction "S3_13") (pintype "output"))
      (node (ref "IC16") (pin "11") (pinfunction "I0_11") (pintype "input"))
    )
    (net (code "87") (name "Net-(IC10A-B4)") (class "Default")
      (node (ref "IC10") (pin "15") (pinfunction "B4_15") (pintype "bidirectional"))
      (node (ref "IC13") (pin "10") (pinfunction "S4_10") (pintype "output"))
      (node (ref "IC16") (pin "12") (pinfunction "I1_12") (pintype "input"))
    )
    (net (code "88") (name "Net-(IC10A-B5)") (class "Default")
      (node (ref "IC10") (pin "14") (pinfunction "B5_14") (pintype "bidirectional"))
      (node (ref "IC12") (pin "4") (pinfunction "S1_4") (pintype "output"))
      (node (ref "IC16") (pin "6") (pinfunction "I1_6") (pintype "input"))
    )
    (net (code "89") (name "Net-(IC10A-B6)") (class "Default")
      (node (ref "IC10") (pin "13") (pinfunction "B6_13") (pintype "bidirectional"))
      (node (ref "IC12") (pin "1") (pinfunction "S2_1") (pintype "output"))
      (node (ref "IC16") (pin "5") (pinfunction "I0_5") (pintype "input"))
    )
    (net (code "90") (name "Net-(IC10A-B7)") (class "Default")
      (node (ref "IC10") (pin "12") (pinfunction "B7_12") (pintype "bidirectional"))
      (node (ref "IC12") (pin "13") (pinfunction "S3_13") (pintype "output"))
      (node (ref "IC16") (pin "3") (pinfunction "I1_3") (pintype "input"))
    )
    (net (code "91") (name "Net-(IC10A-B8)") (class "Default")
      (node (ref "IC10") (pin "11") (pinfunction "B8_11") (pintype "bidirectional"))
      (node (ref "IC12") (pin "10") (pinfunction "S4_10") (pintype "output"))
      (node (ref "IC16") (pin "2") (pinfunction "I0_2") (pintype "input"))
    )
    (net (code "92") (name "Net-(IC11A-O)") (class "Default")
      (node (ref "IC11") (pin "3") (pinfunction "O_3") (pintype "output"))
      (node (ref "IC13") (pin "11") (pinfunction "B4_11") (pintype "input"))
    )
    (net (code "93") (name "Net-(IC11B-O)") (class "Default")
      (node (ref "IC11") (pin "6") (pinfunction "O_6") (pintype "output"))
      (node (ref "IC13") (pin "15") (pinfunction "B3_15") (pintype "input"))
    )
    (net (code "94") (name "Net-(IC11C-O)") (class "Default")
      (node (ref "IC11") (pin "8") (pinfunction "O_8") (pintype "output"))
      (node (ref "IC12") (pin "6") (pinfunction "B1_6") (pintype "input"))
    )
    (net (code "95") (name "Net-(IC11D-O)") (class "Default")
      (node (ref "IC11") (pin "11") (pinfunction "O_11") (pintype "output"))
      (node (ref "IC12") (pin "2") (pinfunction "B2_2") (pintype "input"))
    )
    (net (code "96") (name "Net-(IC12A-B3)") (class "Default")
      (node (ref "IC12") (pin "15") (pinfunction "B3_15") (pintype "input"))
      (node (ref "IC14") (pin "6") (pinfunction "O_6") (pintype "output"))
    )
    (net (code "97") (name "Net-(IC12A-B4)") (class "Default")
      (node (ref "IC12") (pin "11") (pinfunction "B4_11") (pintype "input"))
      (node (ref "IC14") (pin "8") (pinfunction "O_8") (pintype "output"))
    )
    (net (code "98") (name "Net-(IC12A-C0)") (class "Default")
      (node (ref "IC12") (pin "7") (pinfunction "C0_7") (pintype "input"))
      (node (ref "IC13") (pin "9") (pinfunction "C4_9") (pintype "output"))
    )
    (net (code "99") (name "Net-(IC12A-C4)") (class "Default")
      (node (ref "IC12") (pin "9") (pinfunction "C4_9") (pintype "output"))
      (node (ref "IC15") (pin "14") (pinfunction "D1_14") (pintype "input"))
    )
    (net (code "100") (name "Net-(IC13A-B1)") (class "Default")
      (node (ref "IC13") (pin "6") (pinfunction "B1_6") (pintype "input"))
      (node (ref "IC14") (pin "11") (pinfunction "O_11") (pintype "output"))
    )
    (net (code "101") (name "Net-(IC13A-B2)") (class "Default")
      (node (ref "IC13") (pin "2") (pinfunction "B2_2") (pintype "input"))
      (node (ref "IC14") (pin "3") (pinfunction "O_3") (pintype "output"))
    )
    (net (code "102") (name "Net-(IC15A-D2)") (class "Default")
      (node (ref "IC15") (pin "13") (pinfunction "D2_13") (pintype "input"))
      (node (ref "IC17") (pin "8") (pinfunction "O_8") (pintype "output"))
    )
    (net (code "103") (name "Net-(IC16A-O)") (class "Default")
      (node (ref "IC16") (pin "1") (pinfunction "O_1") (pintype "output"))
      (node (ref "IC17") (pin "1") (pinfunction "I0_1") (pintype "input"))
    )
    (net (code "104") (name "Net-(IC16B-O)") (class "Default")
      (node (ref "IC16") (pin "4") (pinfunction "O_4") (pintype "output"))
      (node (ref "IC17") (pin "2") (pinfunction "I1_2") (pintype "input"))
    )
    (net (code "105") (name "Net-(IC16C-O)") (class "Default")
      (node (ref "IC16") (pin "10") (pinfunction "O_10") (pintype "output"))
      (node (ref "IC17") (pin "4") (pinfunction "I0_4") (pintype "input"))
    )
    (net (code "106") (name "Net-(IC16D-O)") (class "Default")
      (node (ref "IC16") (pin "13") (pinfunction "O_13") (pintype "output"))
      (node (ref "IC17") (pin "5") (pinfunction "I1_5") (pintype "input"))
    )
    (net (code "107") (name "Net-(IC17A-O)") (class "Default")
      (node (ref "IC17") (pin "3") (pinfunction "O_3") (pintype "output"))
      (node (ref "IC17") (pin "9") (pinfunction "I0_9") (pintype "input"))
    )
    (net (code "108") (name "Net-(IC17B-O)") (class "Default")
      (node (ref "IC17") (pin "10") (pinfunction "I1_10") (pintype "input"))
      (node (ref "IC17") (pin "6") (pinfunction "O_6") (pintype "output"))
    )
    (net (code "109") (name "Net-(IC22A-CLK)") (class "Default")
      (node (ref "IC22") (pin "2") (pinfunction "CLK_2") (pintype "input"))
      (node (ref "IC23") (pin "2") (pinfunction "CLK_2") (pintype "input"))
    )
    (net (code "110") (name "Net-(IC22A-QA)") (class "Default")
      (node (ref "IC22") (pin "14") (pinfunction "QA_14") (pintype "output"))
      (node (ref "IC26") (pin "18") (pinfunction "B1_18") (pintype "bidirectional"))
    )
    (net (code "111") (name "Net-(IC22A-QB)") (class "Default")
      (node (ref "IC22") (pin "13") (pinfunction "QB_13") (pintype "output"))
      (node (ref "IC26") (pin "17") (pinfunction "B2_17") (pintype "bidirectional"))
    )
    (net (code "112") (name "Net-(IC22A-QC)") (class "Default")
      (node (ref "IC22") (pin "12") (pinfunction "QC_12") (pintype "output"))
      (node (ref "IC26") (pin "16") (pinfunction "B3_16") (pintype "bidirectional"))
    )
    (net (code "113") (name "Net-(IC22A-QD)") (class "Default")
      (node (ref "IC22") (pin "11") (pinfunction "QD_11") (pintype "output"))
      (node (ref "IC26") (pin "15") (pinfunction "B4_15") (pintype "bidirectional"))
    )
    (net (code "114") (name "Net-(IC22A-RCO)") (class "Default")
      (node (ref "IC22") (pin "15") (pinfunction "RCO_15") (pintype "output"))
      (node (ref "IC23") (pin "10") (pinfunction "ENT_10") (pintype "input"))
      (node (ref "IC23") (pin "7") (pinfunction "ENP_7") (pintype "input"))
    )
    (net (code "115") (name "Net-(IC23A-QA)") (class "Default")
      (node (ref "IC23") (pin "14") (pinfunction "QA_14") (pintype "output"))
      (node (ref "IC26") (pin "14") (pinfunction "B5_14") (pintype "bidirectional"))
    )
    (net (code "116") (name "Net-(IC23A-QB)") (class "Default")
      (node (ref "IC23") (pin "13") (pinfunction "QB_13") (pintype "output"))
      (node (ref "IC26") (pin "13") (pinfunction "B6_13") (pintype "bidirectional"))
    )
    (net (code "117") (name "Net-(IC23A-QC)") (class "Default")
      (node (ref "IC23") (pin "12") (pinfunction "QC_12") (pintype "output"))
      (node (ref "IC26") (pin "12") (pinfunction "B7_12") (pintype "bidirectional"))
    )
    (net (code "118") (name "Net-(IC23A-QD)") (class "Default")
      (node (ref "IC23") (pin "11") (pinfunction "QD_11") (pintype "output"))
      (node (ref "IC26") (pin "11") (pinfunction "B8_11") (pintype "bidirectional"))
    )
    (net (code "119") (name "Net-(IC27A-I)") (class "Default")
      (node (ref "IC27") (pin "1") (pinfunction "I_1") (pintype "input"))
      (node (ref "U3") (pin "18") (pinfunction "IO6_18") (pintype "bidirectional"))
    )
    (net (code "120") (name "Net-(IC27B-I)") (class "Default")
      (node (ref "IC27") (pin "3") (pinfunction "I_3") (pintype "input"))
      (node (ref "U3") (pin "15") (pinfunction "IO3_15") (pintype "bidirectional"))
    )
    (net (code "121") (name "Net-(IC27C-I)") (class "Default")
      (node (ref "IC27") (pin "5") (pinfunction "I_5") (pintype "input"))
      (node (ref "U3") (pin "12") (pinfunction "IO1_12") (pintype "bidirectional"))
    )
    (net (code "122") (name "Net-(IC27D-I)") (class "Default")
      (node (ref "IC27") (pin "9") (pinfunction "I_9") (pintype "input"))
      (node (ref "U1") (pin "18") (pinfunction "IO6_18") (pintype "bidirectional"))
    )
    (net (code "123") (name "Net-(IC27E-I)") (class "Default")
      (node (ref "IC27") (pin "11") (pinfunction "I_11") (pintype "input"))
      (node (ref "U3") (pin "11") (pinfunction "IO0_11") (pintype "bidirectional"))
    )
    (net (code "124") (name "Net-(IC27F-I)") (class "Default")
      (node (ref "IC27") (pin "13") (pinfunction "I_13") (pintype "input"))
      (node (ref "U3") (pin "16") (pinfunction "IO4_16") (pintype "bidirectional"))
    )
    (net (code "125") (name "Net-(IC28A-I)") (class "Default")
      (node (ref "IC28") (pin "1") (pinfunction "I_1") (pintype "input"))
      (node (ref "U1") (pin "17") (pinfunction "IO5_17") (pintype "bidirectional"))
    )
    (net (code "126") (name "Net-(IC28B-I)") (class "Default")
      (node (ref "IC28") (pin "3") (pinfunction "I_3") (pintype "input"))
      (node (ref "U1") (pin "15") (pinfunction "IO3_15") (pintype "bidirectional"))
    )
    (net (code "127") (name "Net-(IC28C-I)") (class "Default")
      (node (ref "IC28") (pin "5") (pinfunction "I_5") (pintype "input"))
      (node (ref "U1") (pin "13") (pinfunction "IO2_13") (pintype "bidirectional"))
    )
    (net (code "128") (name "Net-(IC28D-I)") (class "Default")
      (node (ref "IC28") (pin "9") (pinfunction "I_9") (pintype "input"))
      (node (ref "U1") (pin "12") (pinfunction "IO1_12") (pintype "bidirectional"))
    )
    (net (code "129") (name "Net-(IC28E-I)") (class "Default")
      (node (ref "IC28") (pin "11") (pinfunction "I_11") (pintype "input"))
      (node (ref "U1") (pin "11") (pinfunction "IO0_11") (pintype "bidirectional"))
    )
    (net (code "130") (name "Net-(IC28F-I)") (class "Default")
      (node (ref "IC28") (pin "13") (pinfunction "I_13") (pintype "input"))
      (node (ref "U2") (pin "18") (pinfunction "IO6_18") (pintype "bidirectional"))
    )
    (net (code "131") (name "Net-(IC29A-I)") (class "Default")
      (node (ref "IC29") (pin "1") (pinfunction "I_1") (pintype "input"))
      (node (ref "U2") (pin "16") (pinfunction "IO4_16") (pintype "bidirectional"))
    )
    (net (code "132") (name "Net-(IC29B-I)") (class "Default")
      (node (ref "IC29") (pin "3") (pinfunction "I_3") (pintype "input"))
      (node (ref "U2") (pin "12") (pinfunction "IO1_12") (pintype "bidirectional"))
    )
    (net (code "133") (name "Net-(IC29C-I)") (class "Default")
      (node (ref "IC29") (pin "5") (pinfunction "I_5") (pintype "input"))
      (node (ref "U2") (pin "11") (pinfunction "IO0_11") (pintype "bidirectional"))
    )
    (net (code "134") (name "Net-(IC30A-QA)") (class "Default")
      (node (ref "IC30") (pin "14") (pinfunction "QA_14") (pintype "output"))
      (node (ref "U1") (pin "3") (pinfunction "A7_3") (pintype "bidirectional"))
      (node (ref "U2") (pin "3") (pinfunction "A7_3") (pintype "bidirectional"))
      (node (ref "U3") (pin "3") (pinfunction "A7_3") (pintype "bidirectional"))
    )
    (net (code "135") (name "Net-(IC30A-QB)") (class "Default")
      (node (ref "IC30") (pin "13") (pinfunction "QB_13") (pintype "output"))
      (node (ref "U1") (pin "4") (pinfunction "A6_4") (pintype "bidirectional"))
      (node (ref "U2") (pin "4") (pinfunction "A6_4") (pintype "bidirectional"))
      (node (ref "U3") (pin "4") (pinfunction "A6_4") (pintype "bidirectional"))
    )
    (net (code "136") (name "Net-(IC30A-QC)") (class "Default")
      (node (ref "IC30") (pin "12") (pinfunction "QC_12") (pintype "output"))
      (node (ref "U1") (pin "5") (pinfunction "A5_5") (pintype "bidirectional"))
      (node (ref "U2") (pin "5") (pinfunction "A5_5") (pintype "bidirectional"))
      (node (ref "U3") (pin "5") (pinfunction "A5_5") (pintype "bidirectional"))
    )
    (net (code "137") (name "Net-(IC30A-QD)") (class "Default")
      (node (ref "IC30") (pin "11") (pinfunction "QD_11") (pintype "output"))
      (node (ref "U1") (pin "6") (pinfunction "A4_6") (pintype "bidirectional"))
      (node (ref "U2") (pin "6") (pinfunction "A4_6") (pintype "bidirectional"))
      (node (ref "U3") (pin "6") (pinfunction "A4_6") (pintype "bidirectional"))
    )
    (net (code "138") (name "RWIO") (class "Default")
      (node (ref "IC18") (pin "1") (pinfunction "DIR_1") (pintype "input"))
      (node (ref "JP2") (pin "2") (pinfunction "2_2") (pintype "passive"))
      (node (ref "U2") (pin "13") (pinfunction "IO2_13") (pintype "bidirectional"))
    )
    (net (code "139") (name "VCC") (class "Default")
      (node (ref "IC21") (pin "1") (pinfunction "DIR_1") (pintype "input"))
      (node (ref "IC30") (pin "1") (pinfunction "CLR_1") (pintype "input"))
      (node (ref "IC30") (pin "10") (pinfunction "ENT_10") (pintype "input"))
      (node (ref "IC30") (pin "7") (pinfunction "ENP_7") (pintype "input"))
      (node (ref "IC30") (pin "9") (pinfunction "LD_9") (pintype "input"))
      (node (ref "IC5") (pin "1") (pinfunction "DIR_1") (pintype "input"))
      (node (ref "IC6") (pin "1") (pinfunction "DIR_1") (pintype "input"))
      (node (ref "IC9") (pin "1") (pinfunction "DIR_1") (pintype "input"))
      (node (ref "POWER") (pin "1") (pinfunction "1_1") (pintype "passive"))
      (node (ref "U1") (pin "1") (pinfunction "A14_1") (pintype "bidirectional"))
      (node (ref "U1") (pin "27") (pinfunction "~{WE}_27") (pintype "bidirectional"))
      (node (ref "U2") (pin "27") (pinfunction "~{WE}_27") (pintype "bidirectional"))
      (node (ref "U3") (pin "26") (pinfunction "A13_26") (pintype "bidirectional"))
      (node (ref "U3") (pin "27") (pinfunction "~{WE}_27") (pintype "bidirectional"))
    )
    (net (code "140") (name "unconnected-(IC15A-D3-Pad12)") (class "Default")
      (node (ref "IC15") (pin "12") (pinfunction "D3_12") (pintype "input"))
    )
    (net (code "141") (name "unconnected-(IC15A-D4-Pad11)") (class "Default")
      (node (ref "IC15") (pin "11") (pinfunction "D4_11") (pintype "input"))
    )
    (net (code "142") (name "unconnected-(IC15A-Q3-Pad5)") (class "Default")
      (node (ref "IC15") (pin "5") (pinfunction "Q3_5") (pintype "tri_state"))
    )
    (net (code "143") (name "unconnected-(IC15A-Q4-Pad6)") (class "Default")
      (node (ref "IC15") (pin "6") (pinfunction "Q4_6") (pintype "tri_state"))
    )
    (net (code "144") (name "unconnected-(IC23A-RCO-Pad15)") (class "Default")
      (node (ref "IC23") (pin "15") (pinfunction "RCO_15") (pintype "output"))
    )
    (net (code "145") (name "unconnected-(IC24A-CLR-Pad15)") (class "Default")
      (node (ref "IC24") (pin "15") (pinfunction "CLR_15") (pintype "input"))
    )
    (net (code "146") (name "unconnected-(IC25A-CLR-Pad15)") (class "Default")
      (node (ref "IC25") (pin "15") (pinfunction "CLR_15") (pintype "input"))
    )
    (net (code "147") (name "unconnected-(IC30A-A-Pad3)") (class "Default")
      (node (ref "IC30") (pin "3") (pinfunction "A_3") (pintype "input"))
    )
    (net (code "148") (name "unconnected-(IC30A-B-Pad4)") (class "Default")
      (node (ref "IC30") (pin "4") (pinfunction "B_4") (pintype "input"))
    )
    (net (code "149") (name "unconnected-(IC30A-C-Pad5)") (class "Default")
      (node (ref "IC30") (pin "5") (pinfunction "C_5") (pintype "input"))
    )
    (net (code "150") (name "unconnected-(IC30A-D-Pad6)") (class "Default")
      (node (ref "IC30") (pin "6") (pinfunction "D_6") (pintype "input"))
    )
    (net (code "151") (name "unconnected-(IC30A-RCO-Pad15)") (class "Default")
      (node (ref "IC30") (pin "15") (pinfunction "RCO_15") (pintype "output"))
    )
    (net (code "152") (name "unconnected-(U1-GND-Pad14)") (class "Default")
      (node (ref "U1") (pin "14") (pinfunction "GND_14") (pintype "bidirectional"))
    )
    (net (code "153") (name "unconnected-(U1-VCC-Pad28)") (class "Default")
      (node (ref "U1") (pin "28") (pinfunction "VCC_28") (pintype "bidirectional"))
    )
    (net (code "154") (name "unconnected-(U2-GND-Pad14)") (class "Default")
      (node (ref "U2") (pin "14") (pinfunction "GND_14") (pintype "bidirectional"))
    )
    (net (code "155") (name "unconnected-(U2-VCC-Pad28)") (class "Default")
      (node (ref "U2") (pin "28") (pinfunction "VCC_28") (pintype "bidirectional"))
    )
    (net (code "156") (name "unconnected-(U3-GND-Pad14)") (class "Default")
      (node (ref "U3") (pin "14") (pinfunction "GND_14") (pintype "bidirectional"))
    )
    (net (code "157") (name "unconnected-(U3-VCC-Pad28)") (class "Default")
      (node (ref "U3") (pin "28") (pinfunction "VCC_28") (pintype "bidirectional"))
    )
  )
)
